# Receiver.net
KiCad netlist of a schematic drawn in Altium Designer
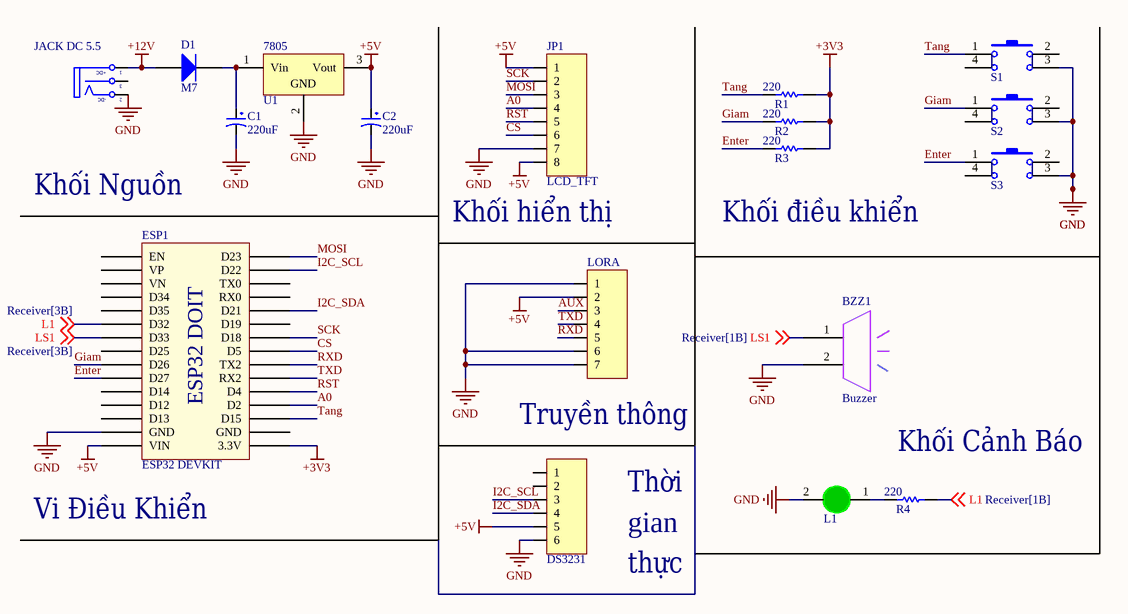
[diagram p0: Receiver.SchDoc]

(export (version "E")
  (design (tool "Eeschema 10.0.6"))
  (components
    (comp (ref "BZZ1")
      (value "Buzzer")
      (footprint "buzzer 5V")
      (libsource (lib "My library altium") (part "Buzzer"))
    )
    (comp (ref "C1")
      (value "220uF")
      (footprint "Tu hoa 8mm")
      (description "Cắm")
      (libsource (lib "Altium_Lib_by_KhueNguyenCreator") (part "Tu Hoa 220uF 25V 8x10"))
    )
    (comp (ref "C2")
      (value "220uF")
      (footprint "Tu hoa 8mm")
      (description "Cắm")
      (libsource (lib "Altium_Lib_by_KhueNguyenCreator") (part "Tu Hoa 220uF 25V 8x10"))
    )
    (comp (ref "D1")
      (value "M7")
      (footprint "DIODE SMA")
      (description "Dán")
      (libsource (lib "Altium_Lib_by_KhueNguyenCreator") (part "Diode M7 ( 4007 )"))
    )
    (comp (ref "ESP1")
      (value "ESP32 DEVKIT")
      (footprint "ESP32 WROOM 32 KIT")
      (libsource (lib "Altium_Lib_by_KhueNguyenCreator") (part "ESP32 WROOM 32 KIT"))
    )
    (comp (ref "JACK DC1")
      (value "JACK DC 5.5")
      (footprint "JACK DC 5.5")
      (libsource (lib "Altium_Lib_by_KhueNguyenCreator") (part "JACK DC 5.5"))
    )
    (comp (ref "JP1")
      (value "LCD_TFT")
      (footprint "JP 1x8 CT")
      (description "Cắm")
      (libsource (lib "Altium_Lib_by_KhueNguyenCreator") (part "JP 1x8 2.54 Cai Thang"))
    )
    (comp (ref "JP2")
      (value "LORA")
      (footprint "JP 1x7 CT")
      (description "Cắm")
      (libsource (lib "Altium_Lib_by_KhueNguyenCreator") (part "JP 1x7 2.54 Cai Thang"))
    )
    (comp (ref "JP3")
      (value "DS3231")
      (footprint "JP 1x6 CT")
      (description "Cắm")
      (libsource (lib "Altium_Lib_by_KhueNguyenCreator") (part "JP 1x6 2.54 Cai Thang"))
    )
    (comp (ref "L1")
      (value "LED 5mm")
      (footprint "LED-5MM-Green")
      (description "Cắm")
      (libsource (lib "Altium_Lib_by_KhueNguyenCreator") (part "LED 5mm Xanh La"))
    )
    (comp (ref "R1")
      (value "220")
      (footprint "ThuvienPCB:0805")
      (libsource (lib "THU VIEN NGUYEN LY") (part "DIENTRO 0.6W"))
    )
    (comp (ref "R2")
      (value "220")
      (footprint "ThuvienPCB:0805")
      (libsource (lib "THU VIEN NGUYEN LY") (part "DIENTRO 0.6W"))
    )
    (comp (ref "R3")
      (value "220")
      (footprint "ThuvienPCB:0805")
      (libsource (lib "THU VIEN NGUYEN LY") (part "DIENTRO 0.6W"))
    )
    (comp (ref "R4")
      (value "220")
      (footprint "ThuvienPCB:0805")
      (libsource (lib "THU VIEN NGUYEN LY") (part "DIENTRO 0.6W"))
    )
    (comp (ref "S1")
      (value "BUTTON 4 CHAN")
      (footprint "ThuvienPCB:BUTTON 6x6x5")
      (libsource (lib "THU VIEN NGUYEN LY") (part "BUTTON 4 CHAN"))
    )
    (comp (ref "S2")
      (value "BUTTON 4 CHAN")
      (footprint "ThuvienPCB:BUTTON 6x6x5")
      (libsource (lib "THU VIEN NGUYEN LY") (part "BUTTON 4 CHAN"))
    )
    (comp (ref "S3")
      (value "BUTTON 4 CHAN")
      (footprint "ThuvienPCB:BUTTON 6x6x5")
      (libsource (lib "THU VIEN NGUYEN LY") (part "BUTTON 4 CHAN"))
    )
    (comp (ref "U1")
      (value "7805")
      (footprint "ThuvienPCB:D-PAK")
      (libsource (lib "THU VIEN NGUYEN LY") (part "7805"))
    )
  )
  (nets
    (net (code "1") (name "+3V3") (class "Default")
      (node (ref "ESP1") (pin "16") (pinfunction "3.3V_16") (pintype "passive"))
      (node (ref "R1") (pin "2") (pinfunction "2_2") (pintype "passive"))
      (node (ref "R2") (pin "2") (pinfunction "2_2") (pintype "passive"))
      (node (ref "R3") (pin "2") (pinfunction "2_2") (pintype "passive"))
    )
    (net (code "2") (name "+5V") (class "Default")
      (node (ref "C2") (pin "1") (pinfunction "1_1") (pintype "passive"))
      (node (ref "ESP1") (pin "15") (pinfunction "VIN_15") (pintype "passive"))
      (node (ref "JP1") (pin "1") (pinfunction "1_1") (pintype "passive"))
      (node (ref "JP1") (pin "8") (pinfunction "8_8") (pintype "passive"))
      (node (ref "JP2") (pin "2") (pinfunction "2_2") (pintype "passive"))
      (node (ref "JP3") (pin "5") (pinfunction "5_5") (pintype "passive"))
      (node (ref "U1") (pin "3") (pinfunction "Vout_3") (pintype "passive"))
    )
    (net (code "3") (name "+12V") (class "Default")
      (node (ref "D1") (pin "1") (pinfunction "A_1") (pintype "passive"))
      (node (ref "JACK DC1") (pin "1") (pinfunction "T_1") (pintype "passive"))
    )
    (net (code "4") (name "/A0") (class "Default")
      (node (ref "ESP1") (pin "19") (pinfunction "D2_19") (pintype "passive"))
      (node (ref "JP1") (pin "4") (pinfunction "4_4") (pintype "passive"))
    )
    (net (code "5") (name "/AUX") (class "Default")
      (node (ref "JP2") (pin "3") (pinfunction "3_3") (pintype "passive"))
    )
    (net (code "6") (name "/CS") (class "Default")
      (node (ref "ESP1") (pin "23") (pinfunction "D5_23") (pintype "passive"))
      (node (ref "JP1") (pin "6") (pinfunction "6_6") (pintype "passive"))
    )
    (net (code "7") (name "/Enter") (class "Default")
      (node (ref "ESP1") (pin "10") (pinfunction "D27_10") (pintype "passive"))
      (node (ref "R3") (pin "1") (pinfunction "1_1") (pintype "passive"))
      (node (ref "S3") (pin "1") (pinfunction "1_1") (pintype "passive"))
    )
    (net (code "8") (name "/Giam") (class "Default")
      (node (ref "ESP1") (pin "9") (pinfunction "D26_9") (pintype "passive"))
      (node (ref "R2") (pin "1") (pinfunction "1_1") (pintype "passive"))
      (node (ref "S2") (pin "1") (pinfunction "1_1") (pintype "passive"))
    )
    (net (code "9") (name "/I2C_SCL") (class "Default")
      (node (ref "ESP1") (pin "29") (pinfunction "D22_29") (pintype "passive"))
      (node (ref "JP3") (pin "3") (pinfunction "3_3") (pintype "passive"))
    )
    (net (code "10") (name "/I2C_SDA") (class "Default")
      (node (ref "ESP1") (pin "26") (pinfunction "D21_26") (pintype "passive"))
      (node (ref "JP3") (pin "4") (pinfunction "4_4") (pintype "passive"))
    )
    (net (code "11") (name "/MOSI") (class "Default")
      (node (ref "ESP1") (pin "30") (pinfunction "D23_30") (pintype "passive"))
      (node (ref "JP1") (pin "3") (pinfunction "3_3") (pintype "passive"))
    )
    (net (code "12") (name "/RST") (class "Default")
      (node (ref "ESP1") (pin "20") (pinfunction "D4_20") (pintype "passive"))
      (node (ref "JP1") (pin "5") (pinfunction "5_5") (pintype "passive"))
    )
    (net (code "13") (name "/RXD") (class "Default")
      (node (ref "ESP1") (pin "22") (pinfunction "TX2_22") (pintype "passive"))
      (node (ref "JP2") (pin "5") (pinfunction "5_5") (pintype "passive"))
    )
    (net (code "14") (name "/SCK") (class "Default")
      (node (ref "ESP1") (pin "24") (pinfunction "D18_24") (pintype "passive"))
      (node (ref "JP1") (pin "2") (pinfunction "2_2") (pintype "passive"))
    )
    (net (code "15") (name "/TXD") (class "Default")
      (node (ref "ESP1") (pin "21") (pinfunction "RX2_21") (pintype "passive"))
      (node (ref "JP2") (pin "4") (pinfunction "4_4") (pintype "passive"))
    )
    (net (code "16") (name "/Tang") (class "Default")
      (node (ref "ESP1") (pin "18") (pinfunction "D15_18") (pintype "passive"))
      (node (ref "R1") (pin "1") (pinfunction "1_1") (pintype "passive"))
      (node (ref "S1") (pin "1") (pinfunction "1_1") (pintype "passive"))
    )
    (net (code "17") (name "GND") (class "Default")
      (node (ref "BZZ1") (pin "2") (pinfunction "2_2") (pintype "passive"))
      (node (ref "C1") (pin "2") (pinfunction "2_2") (pintype "passive"))
      (node (ref "C2") (pin "2") (pinfunction "2_2") (pintype "passive"))
      (node (ref "ESP1") (pin "14") (pinfunction "GND_14") (pintype "passive"))
      (node (ref "JACK DC1") (pin "2") (pinfunction "TN_2") (pintype "passive"))
      (node (ref "JP1") (pin "7") (pinfunction "7_7") (pintype "passive"))
      (node (ref "JP2") (pin "1") (pinfunction "1_1") (pintype "passive"))
      (node (ref "JP2") (pin "6") (pinfunction "6_6") (pintype "passive"))
      (node (ref "JP2") (pin "7") (pinfunction "7_7") (pintype "passive"))
      (node (ref "JP3") (pin "6") (pinfunction "6_6") (pintype "passive"))
      (node (ref "L1") (pin "2") (pinfunction "K_2") (pintype "passive"))
      (node (ref "S1") (pin "3") (pinfunction "3_3") (pintype "passive"))
      (node (ref "S2") (pin "3") (pinfunction "3_3") (pintype "passive"))
      (node (ref "S3") (pin "3") (pinfunction "3_3") (pintype "passive"))
      (node (ref "U1") (pin "2") (pinfunction "GND_2") (pintype "passive"))
    )
    (net (code "18") (name "L1") (class "Default")
      (node (ref "ESP1") (pin "6") (pinfunction "D32_6") (pintype "passive"))
      (node (ref "R4") (pin "2") (pinfunction "2_2") (pintype "passive"))
    )
    (net (code "19") (name "LS1") (class "Default")
      (node (ref "BZZ1") (pin "1") (pinfunction "1_1") (pintype "passive"))
      (node (ref "ESP1") (pin "7") (pinfunction "D33_7") (pintype "passive"))
    )
    (net (code "20") (name "Net-(D1-K)") (class "Default")
      (node (ref "C1") (pin "1") (pinfunction "1_1") (pintype "passive"))
      (node (ref "D1") (pin "2") (pinfunction "K_2") (pintype "passive"))
      (node (ref "U1") (pin "1") (pinfunction "Vin_1") (pintype "passive"))
    )
    (net (code "21") (name "Net-(L1-A)") (class "Default")
      (node (ref "L1") (pin "1") (pinfunction "A_1") (pintype "passive"))
      (node (ref "R4") (pin "1") (pinfunction "1_1") (pintype "passive"))
    )
    (net (code "22") (name "unconnected-(ESP1-D12-Pad12)") (class "Default")
      (node (ref "ESP1") (pin "12") (pinfunction "D12_12") (pintype "passive"))
    )
    (net (code "23") (name "unconnected-(ESP1-D13-Pad13)") (class "Default")
      (node (ref "ESP1") (pin "13") (pinfunction "D13_13") (pintype "passive"))
    )
    (net (code "24") (name "unconnected-(ESP1-D14-Pad11)") (class "Default")
      (node (ref "ESP1") (pin "11") (pinfunction "D14_11") (pintype "passive"))
    )
    (net (code "25") (name "unconnected-(ESP1-D19-Pad25)") (class "Default")
      (node (ref "ESP1") (pin "25") (pinfunction "D19_25") (pintype "passive"))
    )
    (net (code "26") (name "unconnected-(ESP1-D25-Pad8)") (class "Default")
      (node (ref "ESP1") (pin "8") (pinfunction "D25_8") (pintype "passive"))
    )
    (net (code "27") (name "unconnected-(ESP1-D34-Pad4)") (class "Default")
      (node (ref "ESP1") (pin "4") (pinfunction "D34_4") (pintype "passive"))
    )
    (net (code "28") (name "unconnected-(ESP1-D35-Pad5)") (class "Default")
      (node (ref "ESP1") (pin "5") (pinfunction "D35_5") (pintype "passive"))
    )
    (net (code "29") (name "unconnected-(ESP1-EN-Pad1)") (class "Default")
      (node (ref "ESP1") (pin "1") (pinfunction "EN_1") (pintype "passive"))
    )
    (net (code "30") (name "unconnected-(ESP1-GND-Pad17)") (class "Default")
      (node (ref "ESP1") (pin "17") (pinfunction "GND_17") (pintype "passive"))
    )
    (net (code "31") (name "unconnected-(ESP1-RX0-Pad27)") (class "Default")
      (node (ref "ESP1") (pin "27") (pinfunction "RX0_27") (pintype "passive"))
    )
    (net (code "32") (name "unconnected-(ESP1-TX0-Pad28)") (class "Default")
      (node (ref "ESP1") (pin "28") (pinfunction "TX0_28") (pintype "passive"))
    )
    (net (code "33") (name "unconnected-(ESP1-VN-Pad3)") (class "Default")
      (node (ref "ESP1") (pin "3") (pinfunction "VN_3") (pintype "passive"))
    )
    (net (code "34") (name "unconnected-(ESP1-VP-Pad2)") (class "Default")
      (node (ref "ESP1") (pin "2") (pinfunction "VP_2") (pintype "passive"))
    )
    (net (code "35") (name "unconnected-(JACK DC1-S-Pad3)") (class "Default")
      (node (ref "JACK DC1") (pin "3") (pinfunction "S_3") (pintype "power_in"))
    )
    (net (code "36") (name "unconnected-(JP3-Pad1)") (class "Default")
      (node (ref "JP3") (pin "1") (pinfunction "1_1") (pintype "passive"))
    )
    (net (code "37") (name "unconnected-(JP3-Pad2)") (class "Default")
      (node (ref "JP3") (pin "2") (pinfunction "2_2") (pintype "passive"))
    )
    (net (code "38") (name "unconnected-(S1-Pad2)") (class "Default")
      (node (ref "S1") (pin "2") (pinfunction "2_2") (pintype "passive"))
    )
    (net (code "39") (name "unconnected-(S1-Pad4)") (class "Default")
      (node (ref "S1") (pin "4") (pinfunction "4_4") (pintype "passive"))
    )
    (net (code "40") (name "unconnected-(S2-Pad2)") (class "Default")
      (node (ref "S2") (pin "2") (pinfunction "2_2") (pintype "passive"))
    )
    (net (code "41") (name "unconnected-(S2-Pad4)") (class "Default")
      (node (ref "S2") (pin "4") (pinfunction "4_4") (pintype "passive"))
    )
    (net (code "42") (name "unconnected-(S3-Pad2)") (class "Default")
      (node (ref "S3") (pin "2") (pinfunction "2_2") (pintype "passive"))
    )
    (net (code "43") (name "unconnected-(S3-Pad4)") (class "Default")
      (node (ref "S3") (pin "4") (pinfunction "4_4") (pintype "passive"))
    )
  )
)
